# 2_4G8_2.net
KiCad netlist of a schematic drawn in EasyEDA Pro
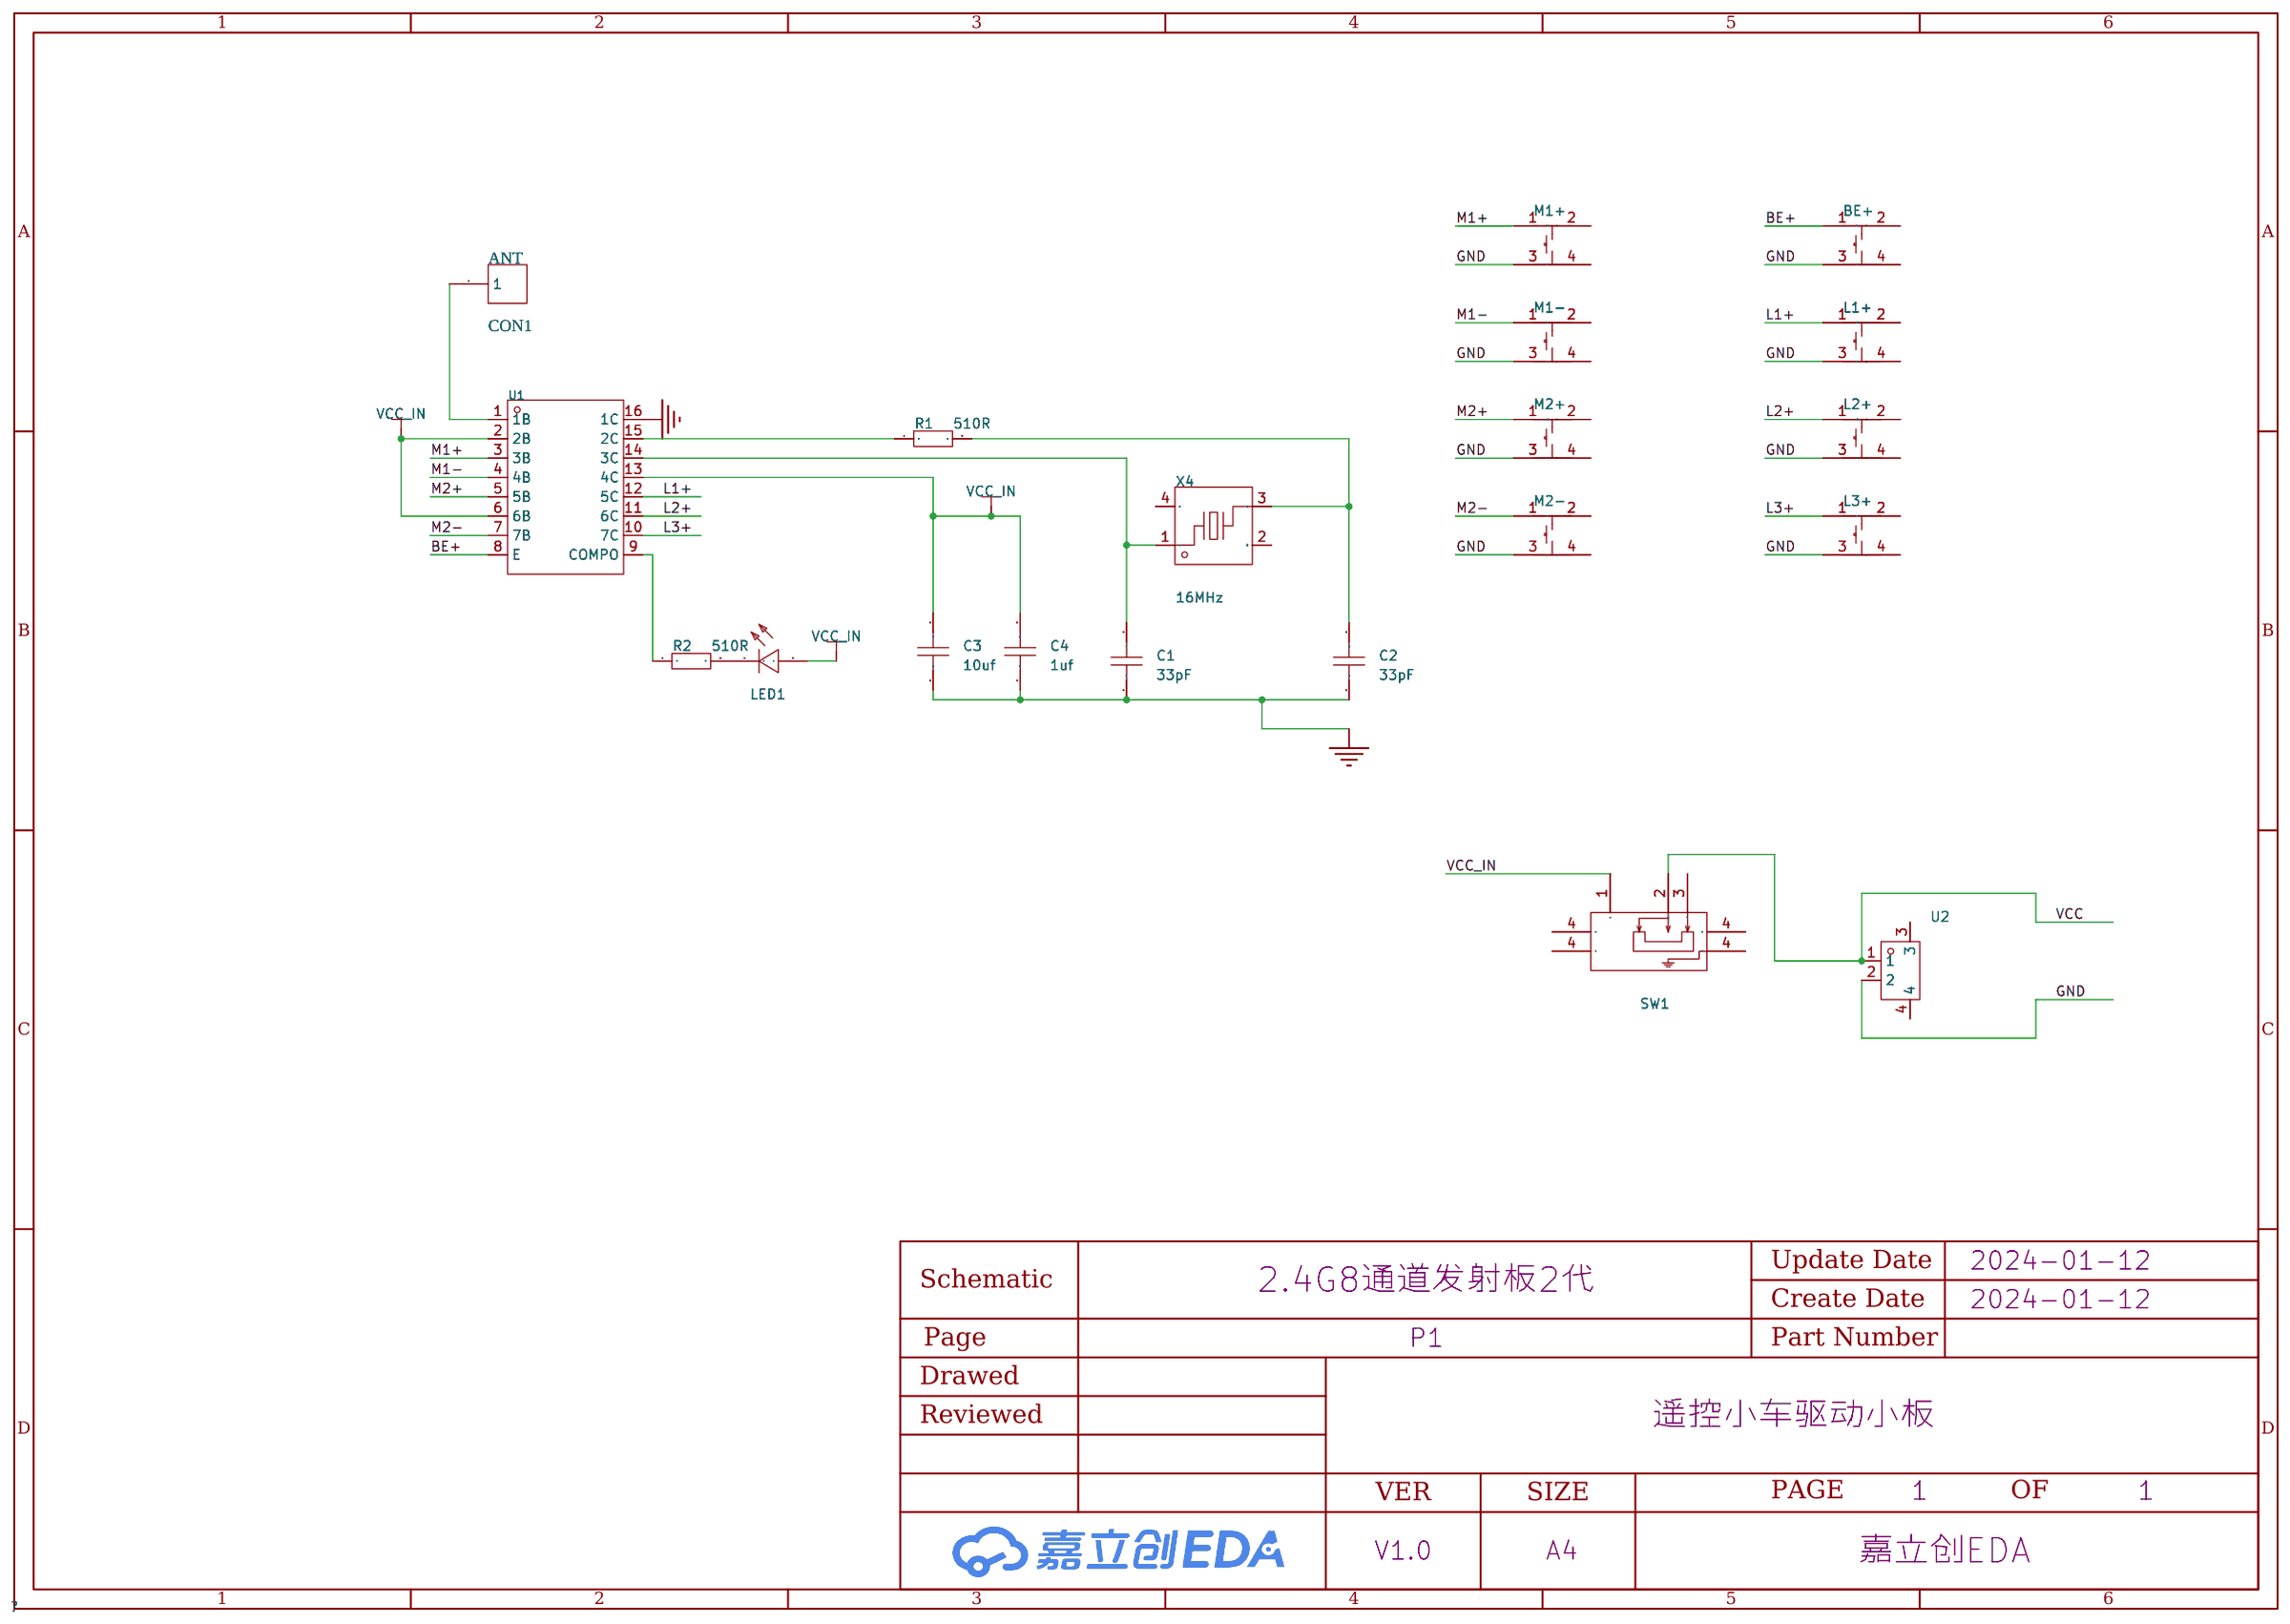
[diagram p0: schematic sheet]

(export (version "E")
  (design (tool "Eeschema 10.0.6"))
  (components
    (comp (ref "ANT")
      (value "CON1")
      (footprint "easyedapro:CON1_2")
      (libsource (lib "easyedapro") (part "CON1"))
    )
    (comp (ref "BE+")
      (value "TS-1095S-A1B3-C2D1")
      (footprint "easyedapro:SW-SMD_4P-L6.0-W6.0-P4.50-LS8.5")
      (description "电路结构:单刀单掷;按钮作用方向:顶部触动;致动器样式:圆形按钮;照明颜色:-;作用力:250gf ±30gf;开关长度:6mm;开关宽度:6mm;开关高度:4.3mm;")
      (fields (field (name "Manufacturer") "Yuandi(元迪)"))
      (libsource (lib "easyedapro") (part "TS-1095S-A1B3-C2D1"))
    )
    (comp (ref "C1")
      (value "33pF")
      (footprint "easyedapro:C0603")
      (libsource (lib "easyedapro") (part "CapAcitance"))
    )
    (comp (ref "C2")
      (value "33pF")
      (footprint "easyedapro:C0603")
      (libsource (lib "easyedapro") (part "CapAcitance"))
    )
    (comp (ref "C3")
      (value "10uf")
      (footprint "easyedapro:C0603")
      (libsource (lib "easyedapro") (part "CapAcitance"))
    )
    (comp (ref "C4")
      (value "1uf")
      (footprint "easyedapro:C0603")
      (libsource (lib "easyedapro") (part "CapAcitance"))
    )
    (comp (ref "L1+")
      (value "TS-1095S-A1B3-C2D1")
      (footprint "easyedapro:SW-SMD_4P-L6.0-W6.0-P4.50-LS8.5")
      (description "电路结构:单刀单掷;按钮作用方向:顶部触动;致动器样式:圆形按钮;照明颜色:-;作用力:250gf ±30gf;开关长度:6mm;开关宽度:6mm;开关高度:4.3mm;")
      (fields (field (name "Manufacturer") "Yuandi(元迪)"))
      (libsource (lib "easyedapro") (part "TS-1095S-A1B3-C2D1"))
    )
    (comp (ref "L2+")
      (value "TS-1095S-A1B3-C2D1")
      (footprint "easyedapro:SW-SMD_4P-L6.0-W6.0-P4.50-LS8.5")
      (description "电路结构:单刀单掷;按钮作用方向:顶部触动;致动器样式:圆形按钮;照明颜色:-;作用力:250gf ±30gf;开关长度:6mm;开关宽度:6mm;开关高度:4.3mm;")
      (fields (field (name "Manufacturer") "Yuandi(元迪)"))
      (libsource (lib "easyedapro") (part "TS-1095S-A1B3-C2D1"))
    )
    (comp (ref "L3+")
      (value "TS-1095S-A1B3-C2D1")
      (footprint "easyedapro:SW-SMD_4P-L6.0-W6.0-P4.50-LS8.5")
      (description "电路结构:单刀单掷;按钮作用方向:顶部触动;致动器样式:圆形按钮;照明颜色:-;作用力:250gf ±30gf;开关长度:6mm;开关宽度:6mm;开关高度:4.3mm;")
      (fields (field (name "Manufacturer") "Yuandi(元迪)"))
      (libsource (lib "easyedapro") (part "TS-1095S-A1B3-C2D1"))
    )
    (comp (ref "LED1")
      (value "NCD0603R1")
      (footprint "easyedapro:LED0603-RD_RED")
      (description "发光颜色:红色;功率:65mW;透镜颜色:无色透明;主波长:615nm~630nm;发光强度:80mcd~220mcd;发光角度:130°;工作温度:-30°C~+85°C;")
      (fields (field (name "Manufacturer") "国星光电"))
      (libsource (lib "easyedapro") (part "FC-DA1608HRK-620D"))
    )
    (comp (ref "M1+")
      (value "TS-1095S-A1B3-C2D1")
      (footprint "easyedapro:SW-SMD_4P-L6.0-W6.0-P4.50-LS8.5")
      (description "电路结构:单刀单掷;按钮作用方向:顶部触动;致动器样式:圆形按钮;照明颜色:-;作用力:250gf ±30gf;开关长度:6mm;开关宽度:6mm;开关高度:4.3mm;")
      (fields (field (name "Manufacturer") "Yuandi(元迪)"))
      (libsource (lib "easyedapro") (part "TS-1095S-A1B3-C2D1"))
    )
    (comp (ref "M1-")
      (value "TS-1095S-A1B3-C2D1")
      (footprint "easyedapro:SW-SMD_4P-L6.0-W6.0-P4.50-LS8.5")
      (description "电路结构:单刀单掷;按钮作用方向:顶部触动;致动器样式:圆形按钮;照明颜色:-;作用力:250gf ±30gf;开关长度:6mm;开关宽度:6mm;开关高度:4.3mm;")
      (fields (field (name "Manufacturer") "Yuandi(元迪)"))
      (libsource (lib "easyedapro") (part "TS-1095S-A1B3-C2D1"))
    )
    (comp (ref "M2+")
      (value "TS-1095S-A1B3-C2D1")
      (footprint "easyedapro:SW-SMD_4P-L6.0-W6.0-P4.50-LS8.5")
      (description "电路结构:单刀单掷;按钮作用方向:顶部触动;致动器样式:圆形按钮;照明颜色:-;作用力:250gf ±30gf;开关长度:6mm;开关宽度:6mm;开关高度:4.3mm;")
      (fields (field (name "Manufacturer") "Yuandi(元迪)"))
      (libsource (lib "easyedapro") (part "TS-1095S-A1B3-C2D1"))
    )
    (comp (ref "M2-")
      (value "TS-1095S-A1B3-C2D1")
      (footprint "easyedapro:SW-SMD_4P-L6.0-W6.0-P4.50-LS8.5")
      (description "电路结构:单刀单掷;按钮作用方向:顶部触动;致动器样式:圆形按钮;照明颜色:-;作用力:250gf ±30gf;开关长度:6mm;开关宽度:6mm;开关高度:4.3mm;")
      (fields (field (name "Manufacturer") "Yuandi(元迪)"))
      (libsource (lib "easyedapro") (part "TS-1095S-A1B3-C2D1"))
    )
    (comp (ref "R1") (value "510R") (footprint "easyedapro:R0603") (libsource (lib "easyedapro") (part "电阻")))
    (comp (ref "R2") (value "510R") (footprint "easyedapro:R0603") (libsource (lib "easyedapro") (part "电阻")))
    (comp (ref "SW1")
      (value "MSK12C02")
      (footprint "easyedapro:SW-TH_MSK12C02")
      (fields (field (name "Manufacturer") "SHOU HAN(首韩)"))
      (libsource (lib "easyedapro") (part "MSK12C02"))
    )
    (comp (ref "U1")
      (value "ULN2003A")
      (footprint "easyedapro:SOP-16_L10.0-W3.9-P1.27-LS6.0-BL")
      (description "开态输入电压(VI(on)@Vce,Ic):3V@2V,300mA;集射极饱和压降(VCE(sat)@Ii,Ic):900mV;开态输入电流(Ii@Vi):930uA@3.85V;")
      (fields (field (name "Manufacturer") "UMW(友台半导体)"))
      (libsource (lib "easyedapro") (part "ULN2003A_C482013"))
    )
    (comp (ref "U2")
      (value "XD-GH-2PWT")
      (footprint "easyedapro:CONN-SMD_GH-2PWT")
      (description "参考系列:GH;间距:1.25mm;插针结构:1x2P;排数:1;每排PIN数:2;公母:公型插针;安装方式:卧贴;额定电流:1A;触头镀层:锡;工作温度范围:-40°C~+105°C;")
      (fields (field (name "Manufacturer") "XUNDA(讯答)"))
      (libsource (lib "easyedapro") (part "XD-GH-2PWT"))
    )
    (comp (ref "X4")
      (value "16MHz")
      (footprint "easyedapro:CRYSTAL-SMD_4P-L2.0-W1.6-BL")
      (description "晶振类型:贴片无源晶振;频率:16MHz;常温频差:±10ppm;负载电容:12pF;频率稳定度(全温):±20ppm;")
      (fields
        (field (name "Manufacturer Part") "XL7EL89COI-111YLC-16M")
        (field (name "Manufacturer") "YXC(扬兴晶振)")
      )
      (libsource (lib "easyedapro") (part "XL7EL89COI-111YLC-16M"))
    )
  )
  (nets
    (net (code "1") (name "/BE+") (class "Default")
      (node (ref "BE+") (pin "1") (pinfunction "1_1") (pintype "input"))
      (node (ref "U1") (pin "8") (pinfunction "E_8") (pintype "input"))
    )
    (net (code "2") (name "/L1+") (class "Default")
      (node (ref "L1+") (pin "1") (pinfunction "1_1") (pintype "input"))
      (node (ref "U1") (pin "12") (pinfunction "5C_12") (pintype "input"))
    )
    (net (code "3") (name "/L2+") (class "Default")
      (node (ref "L2+") (pin "1") (pinfunction "1_1") (pintype "input"))
      (node (ref "U1") (pin "11") (pinfunction "6C_11") (pintype "input"))
    )
    (net (code "4") (name "/L3+") (class "Default")
      (node (ref "L3+") (pin "1") (pinfunction "1_1") (pintype "input"))
      (node (ref "U1") (pin "10") (pinfunction "7C_10") (pintype "input"))
    )
    (net (code "5") (name "/M1+") (class "Default")
      (node (ref "M1+") (pin "1") (pinfunction "1_1") (pintype "input"))
      (node (ref "U1") (pin "3") (pinfunction "3B_3") (pintype "input"))
    )
    (net (code "6") (name "/M1-") (class "Default")
      (node (ref "M1-") (pin "1") (pinfunction "1_1") (pintype "input"))
      (node (ref "U1") (pin "4") (pinfunction "4B_4") (pintype "input"))
    )
    (net (code "7") (name "/M2+") (class "Default")
      (node (ref "M2+") (pin "1") (pinfunction "1_1") (pintype "input"))
      (node (ref "U1") (pin "5") (pinfunction "5B_5") (pintype "input"))
    )
    (net (code "8") (name "/M2-") (class "Default")
      (node (ref "M2-") (pin "1") (pinfunction "1_1") (pintype "input"))
      (node (ref "U1") (pin "7") (pinfunction "7B_7") (pintype "input"))
    )
    (net (code "9") (name "/VCC") (class "Default")
      (node (ref "SW1") (pin "2") (pinfunction "2_2") (pintype "input"))
      (node (ref "U2") (pin "1") (pinfunction "1_1") (pintype "unspecified"))
    )
    (net (code "10") (name "GND") (class "Default")
      (node (ref "BE+") (pin "3") (pinfunction "3_3") (pintype "input"))
      (node (ref "C1") (pin "1") (pinfunction "1_1") (pintype "input"))
      (node (ref "C2") (pin "1") (pinfunction "1_1") (pintype "input"))
      (node (ref "C3") (pin "1") (pinfunction "1_1") (pintype "input"))
      (node (ref "C4") (pin "1") (pinfunction "1_1") (pintype "input"))
      (node (ref "L1+") (pin "3") (pinfunction "3_3") (pintype "input"))
      (node (ref "L2+") (pin "3") (pinfunction "3_3") (pintype "input"))
      (node (ref "L3+") (pin "3") (pinfunction "3_3") (pintype "input"))
      (node (ref "M1+") (pin "3") (pinfunction "3_3") (pintype "input"))
      (node (ref "M1-") (pin "3") (pinfunction "3_3") (pintype "input"))
      (node (ref "M2+") (pin "3") (pinfunction "3_3") (pintype "input"))
      (node (ref "M2-") (pin "3") (pinfunction "3_3") (pintype "input"))
      (node (ref "U1") (pin "16") (pinfunction "1C_16") (pintype "input"))
      (node (ref "U2") (pin "2") (pinfunction "2_2") (pintype "unspecified"))
    )
    (net (code "11") (name "Net-(C2-Pad2)") (class "Default")
      (node (ref "C2") (pin "2") (pinfunction "2_2") (pintype "input"))
      (node (ref "R1") (pin "2") (pinfunction "2_2") (pintype "input"))
      (node (ref "X4") (pin "3") (pinfunction "3_3") (pintype "input"))
    )
    (net (code "12") (name "Net-(LED1-K)") (class "Default")
      (node (ref "LED1") (pin "1") (pinfunction "K_1") (pintype "input"))
      (node (ref "R2") (pin "2") (pinfunction "2_2") (pintype "input"))
    )
    (net (code "13") (name "Net-(U1-1B)") (class "Default")
      (node (ref "ANT") (pin "1") (pinfunction "1_1") (pintype "input"))
      (node (ref "U1") (pin "1") (pinfunction "1B_1") (pintype "input"))
    )
    (net (code "14") (name "Net-(U1-2C)") (class "Default")
      (node (ref "R1") (pin "1") (pinfunction "1_1") (pintype "input"))
      (node (ref "U1") (pin "15") (pinfunction "2C_15") (pintype "input"))
    )
    (net (code "15") (name "Net-(U1-3C)") (class "Default")
      (node (ref "C1") (pin "2") (pinfunction "2_2") (pintype "input"))
      (node (ref "U1") (pin "14") (pinfunction "3C_14") (pintype "input"))
      (node (ref "X4") (pin "1") (pinfunction "1_1") (pintype "input"))
    )
    (net (code "16") (name "Net-(U1-COMPO)") (class "Default")
      (node (ref "R2") (pin "1") (pinfunction "1_1") (pintype "input"))
      (node (ref "U1") (pin "9") (pinfunction "COMPO_9") (pintype "input"))
    )
    (net (code "17") (name "VCC_IN") (class "Default")
      (node (ref "C3") (pin "2") (pinfunction "2_2") (pintype "input"))
      (node (ref "C4") (pin "2") (pinfunction "2_2") (pintype "input"))
      (node (ref "LED1") (pin "2") (pinfunction "A_2") (pintype "input"))
      (node (ref "SW1") (pin "1") (pinfunction "1_1") (pintype "input"))
      (node (ref "U1") (pin "13") (pinfunction "4C_13") (pintype "input"))
      (node (ref "U1") (pin "2") (pinfunction "2B_2") (pintype "input"))
      (node (ref "U1") (pin "6") (pinfunction "6B_6") (pintype "input"))
    )
    (net (code "18") (name "unconnected-(BE+-Pad2)") (class "Default")
      (node (ref "BE+") (pin "2") (pinfunction "2_2") (pintype "input"))
    )
    (net (code "19") (name "unconnected-(BE+-Pad4)") (class "Default")
      (node (ref "BE+") (pin "4") (pinfunction "4_4") (pintype "input"))
    )
    (net (code "20") (name "unconnected-(L1+-Pad2)") (class "Default")
      (node (ref "L1+") (pin "2") (pinfunction "2_2") (pintype "input"))
    )
    (net (code "21") (name "unconnected-(L1+-Pad4)") (class "Default")
      (node (ref "L1+") (pin "4") (pinfunction "4_4") (pintype "input"))
    )
    (net (code "22") (name "unconnected-(L2+-Pad2)") (class "Default")
      (node (ref "L2+") (pin "2") (pinfunction "2_2") (pintype "input"))
    )
    (net (code "23") (name "unconnected-(L2+-Pad4)") (class "Default")
      (node (ref "L2+") (pin "4") (pinfunction "4_4") (pintype "input"))
    )
    (net (code "24") (name "unconnected-(L3+-Pad2)") (class "Default")
      (node (ref "L3+") (pin "2") (pinfunction "2_2") (pintype "input"))
    )
    (net (code "25") (name "unconnected-(L3+-Pad4)") (class "Default")
      (node (ref "L3+") (pin "4") (pinfunction "4_4") (pintype "input"))
    )
    (net (code "26") (name "unconnected-(M1+-Pad2)") (class "Default")
      (node (ref "M1+") (pin "2") (pinfunction "2_2") (pintype "input"))
    )
    (net (code "27") (name "unconnected-(M1+-Pad4)") (class "Default")
      (node (ref "M1+") (pin "4") (pinfunction "4_4") (pintype "input"))
    )
    (net (code "28") (name "unconnected-(M1--Pad2)") (class "Default")
      (node (ref "M1-") (pin "2") (pinfunction "2_2") (pintype "input"))
    )
    (net (code "29") (name "unconnected-(M1--Pad4)") (class "Default")
      (node (ref "M1-") (pin "4") (pinfunction "4_4") (pintype "input"))
    )
    (net (code "30") (name "unconnected-(M2+-Pad2)") (class "Default")
      (node (ref "M2+") (pin "2") (pinfunction "2_2") (pintype "input"))
    )
    (net (code "31") (name "unconnected-(M2+-Pad4)") (class "Default")
      (node (ref "M2+") (pin "4") (pinfunction "4_4") (pintype "input"))
    )
    (net (code "32") (name "unconnected-(M2--Pad2)") (class "Default")
      (node (ref "M2-") (pin "2") (pinfunction "2_2") (pintype "input"))
    )
    (net (code "33") (name "unconnected-(M2--Pad4)") (class "Default")
      (node (ref "M2-") (pin "4") (pinfunction "4_4") (pintype "input"))
    )
    (net (code "34") (name "unconnected-(SW1-Pad3)") (class "Default")
      (node (ref "SW1") (pin "3") (pinfunction "3_3") (pintype "input"))
    )
    (net (code "35") (name "unconnected-(SW1-Pad4)") (class "Default")
      (node (ref "SW1") (pin "4") (pinfunction "4_4") (pintype "input"))
    )
    (net (code "36") (name "unconnected-(SW1-Pad4)_1") (class "Default")
      (node (ref "SW1") (pin "4") (pinfunction "4_4") (pintype "input"))
    )
    (net (code "37") (name "unconnected-(SW1-Pad4)_2") (class "Default")
      (node (ref "SW1") (pin "4") (pinfunction "4_4") (pintype "input"))
    )
    (net (code "38") (name "unconnected-(SW1-Pad4)_3") (class "Default")
      (node (ref "SW1") (pin "4") (pinfunction "4_4") (pintype "input"))
    )
    (net (code "39") (name "unconnected-(U2-Pad3)") (class "Default")
      (node (ref "U2") (pin "3") (pinfunction "3_3") (pintype "unspecified"))
    )
    (net (code "40") (name "unconnected-(U2-Pad4)") (class "Default")
      (node (ref "U2") (pin "4") (pinfunction "4_4") (pintype "unspecified"))
    )
    (net (code "41") (name "unconnected-(X4-GND-Pad2)") (class "Default")
      (node (ref "X4") (pin "2") (pinfunction "GND_2") (pintype "input"))
    )
    (net (code "42") (name "unconnected-(X4-GND-Pad4)") (class "Default")
      (node (ref "X4") (pin "4") (pinfunction "GND_4") (pintype "input"))
    )
  )
)
